# 19_-CAMERA_PWR_CONNECTORS.net
KiCad netlist of a schematic drawn in Altium Designer
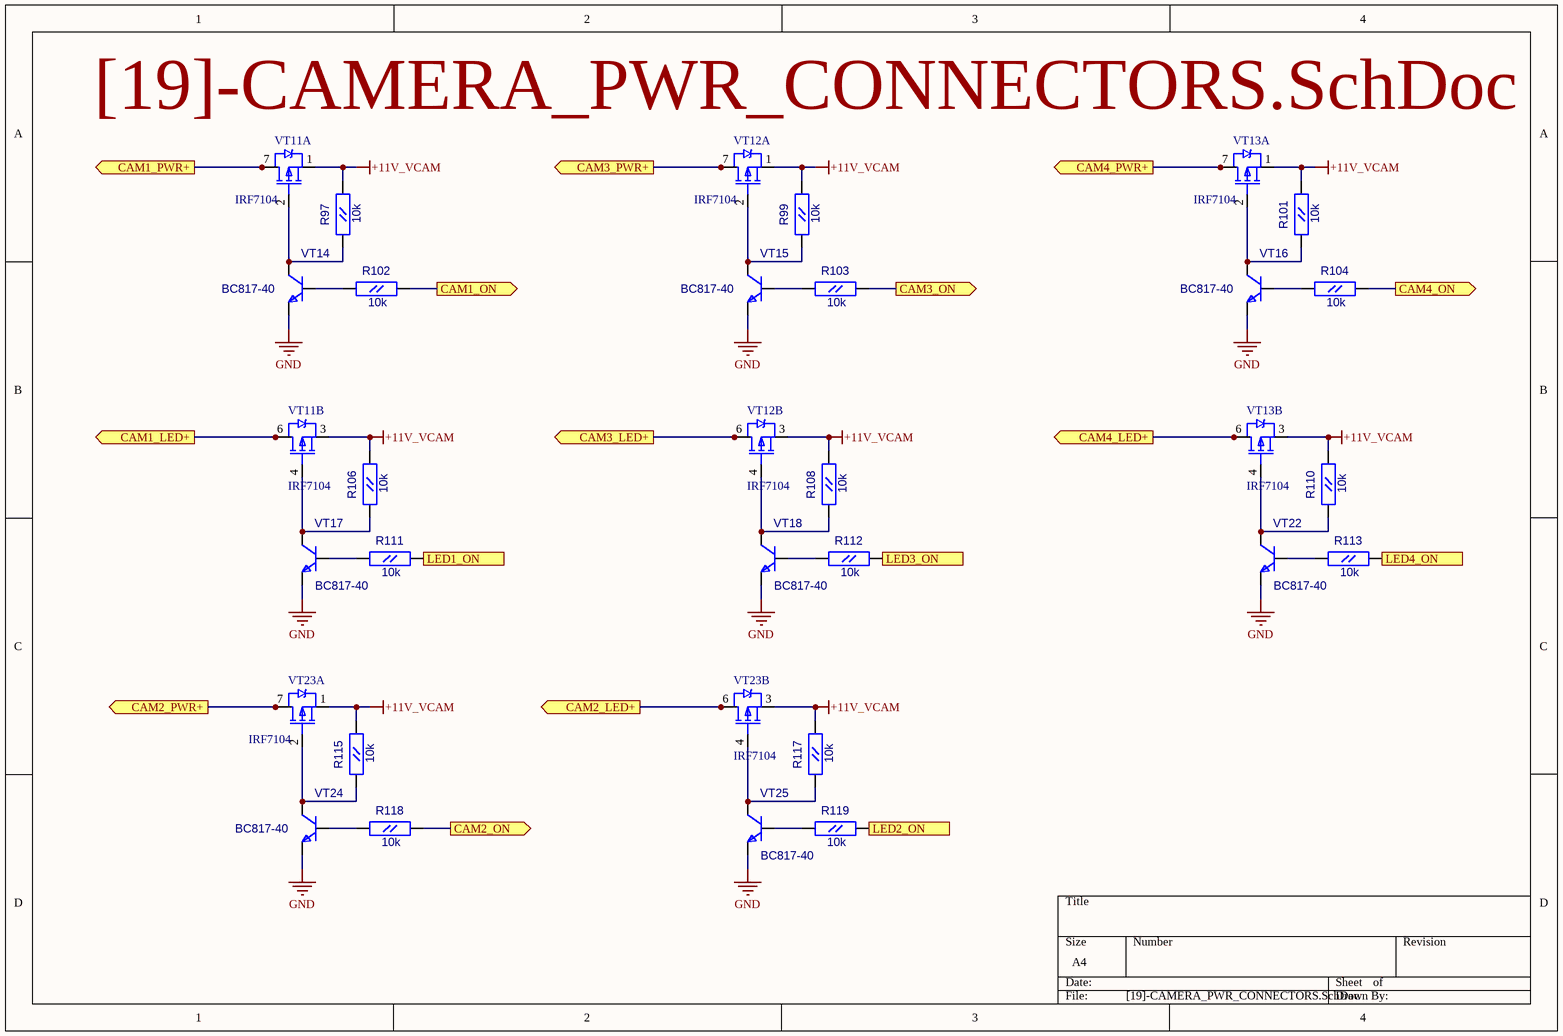
[diagram p0: [19]-CAMERA_PWR_CONNECTORS.SchDoc]

(export (version "E")
  (design (tool "Eeschema 10.0.6"))
  (components
    (comp (ref "R97")
      (value "10k")
      (footprint "RC0603")
      (description "RC0603")
      (libsource (lib "fizik_lib") (part "RC0603"))
    )
    (comp (ref "R99")
      (value "10k")
      (footprint "RC0603")
      (description "RC0603")
      (libsource (lib "fizik_lib") (part "RC0603"))
    )
    (comp (ref "R101")
      (value "10k")
      (footprint "RC0603")
      (description "RC0603")
      (libsource (lib "fizik_lib") (part "RC0603"))
    )
    (comp (ref "R102")
      (value "10k")
      (footprint "RC0603")
      (description "RC0603")
      (libsource (lib "fizik_lib") (part "RC0603"))
    )
    (comp (ref "R103")
      (value "10k")
      (footprint "RC0603")
      (description "RC0603")
      (libsource (lib "fizik_lib") (part "RC0603"))
    )
    (comp (ref "R104")
      (value "10k")
      (footprint "RC0603")
      (description "RC0603")
      (libsource (lib "fizik_lib") (part "RC0603"))
    )
    (comp (ref "R106")
      (value "10k")
      (footprint "RC0603")
      (description "RC0603")
      (libsource (lib "fizik_lib") (part "RC0603"))
    )
    (comp (ref "R108")
      (value "10k")
      (footprint "RC0603")
      (description "RC0603")
      (libsource (lib "fizik_lib") (part "RC0603"))
    )
    (comp (ref "R110")
      (value "10k")
      (footprint "RC0603")
      (description "RC0603")
      (libsource (lib "fizik_lib") (part "RC0603"))
    )
    (comp (ref "R111")
      (value "10k")
      (footprint "RC0603")
      (description "RC0603")
      (libsource (lib "fizik_lib") (part "RC0603"))
    )
    (comp (ref "R112")
      (value "10k")
      (footprint "RC0603")
      (description "RC0603")
      (libsource (lib "fizik_lib") (part "RC0603"))
    )
    (comp (ref "R113")
      (value "10k")
      (footprint "RC0603")
      (description "RC0603")
      (libsource (lib "fizik_lib") (part "RC0603"))
    )
    (comp (ref "R115")
      (value "10k")
      (footprint "RC0603")
      (description "RC0603")
      (libsource (lib "fizik_lib") (part "RC0603"))
    )
    (comp (ref "R117")
      (value "10k")
      (footprint "RC0603")
      (description "RC0603")
      (libsource (lib "fizik_lib") (part "RC0603"))
    )
    (comp (ref "R118")
      (value "10k")
      (footprint "RC0603")
      (description "RC0603")
      (libsource (lib "fizik_lib") (part "RC0603"))
    )
    (comp (ref "R119")
      (value "10k")
      (footprint "RC0603")
      (description "RC0603")
      (libsource (lib "fizik_lib") (part "RC0603"))
    )
    (comp (ref "VT11")
      (value "IRF7104")
      (footprint "SO-8")
      (description "Dual P-channel MOSFET. 20V,2.3A, 0.25Ohm")
      (libsource (lib "fizik_lib (1)") (part "IRF7104"))
    )
    (comp (ref "VT12")
      (value "IRF7104")
      (footprint "SO-8")
      (description "Dual P-channel MOSFET. 20V,2.3A, 0.25Ohm")
      (libsource (lib "fizik_lib (1)") (part "IRF7104"))
    )
    (comp (ref "VT13")
      (value "IRF7104")
      (footprint "SO-8")
      (description "Dual P-channel MOSFET. 20V,2.3A, 0.25Ohm")
      (libsource (lib "fizik_lib (1)") (part "IRF7104"))
    )
    (comp (ref "VT14")
      (value "BC817-40")
      (footprint "SOT-23(123)")
      (description "NPN 500ma transistor")
      (libsource (lib "fizik_lib") (part "BC846BLT1"))
    )
    (comp (ref "VT15")
      (value "BC817-40")
      (footprint "SOT-23(123)")
      (description "NPN 500ma transistor")
      (libsource (lib "fizik_lib") (part "BC846BLT1"))
    )
    (comp (ref "VT16")
      (value "BC817-40")
      (footprint "SOT-23(123)")
      (description "NPN 500ma transistor")
      (libsource (lib "fizik_lib") (part "BC846BLT1"))
    )
    (comp (ref "VT17")
      (value "BC817-40")
      (footprint "SOT-23(123)")
      (description "NPN 500ma transistor")
      (libsource (lib "fizik_lib") (part "BC846BLT1"))
    )
    (comp (ref "VT18")
      (value "BC817-40")
      (footprint "SOT-23(123)")
      (description "NPN 500ma transistor")
      (libsource (lib "fizik_lib") (part "BC846BLT1"))
    )
    (comp (ref "VT22")
      (value "BC817-40")
      (footprint "SOT-23(123)")
      (description "NPN 500ma transistor")
      (libsource (lib "fizik_lib") (part "BC846BLT1"))
    )
    (comp (ref "VT23")
      (value "IRF7104")
      (footprint "SO-8")
      (description "Dual P-channel MOSFET. 20V,2.3A, 0.25Ohm")
      (libsource (lib "fizik_lib (1)") (part "IRF7104"))
    )
    (comp (ref "VT24")
      (value "BC817-40")
      (footprint "SOT-23(123)")
      (description "NPN 500ma transistor")
      (libsource (lib "fizik_lib") (part "BC846BLT1"))
    )
    (comp (ref "VT25")
      (value "BC817-40")
      (footprint "SOT-23(123)")
      (description "NPN 500ma transistor")
      (libsource (lib "fizik_lib") (part "BC846BLT1"))
    )
  )
  (nets
    (net (code "1") (name "+11V_VCAM") (class "Default")
      (node (ref "R101") (pin "2") (pinfunction "B_2") (pintype "passive"))
      (node (ref "R106") (pin "2") (pinfunction "B_2") (pintype "passive"))
      (node (ref "R108") (pin "2") (pinfunction "B_2") (pintype "passive"))
      (node (ref "R110") (pin "2") (pinfunction "B_2") (pintype "passive"))
      (node (ref "R115") (pin "2") (pinfunction "B_2") (pintype "passive"))
      (node (ref "R117") (pin "2") (pinfunction "B_2") (pintype "passive"))
      (node (ref "R97") (pin "2") (pinfunction "B_2") (pintype "passive"))
      (node (ref "R99") (pin "2") (pinfunction "B_2") (pintype "passive"))
      (node (ref "VT11") (pin "1") (pinfunction "S_1") (pintype "passive"))
      (node (ref "VT11") (pin "3") (pinfunction "S_3") (pintype "passive"))
      (node (ref "VT12") (pin "1") (pinfunction "S_1") (pintype "passive"))
      (node (ref "VT12") (pin "3") (pinfunction "S_3") (pintype "passive"))
      (node (ref "VT13") (pin "1") (pinfunction "S_1") (pintype "passive"))
      (node (ref "VT13") (pin "3") (pinfunction "S_3") (pintype "passive"))
      (node (ref "VT23") (pin "1") (pinfunction "S_1") (pintype "passive"))
      (node (ref "VT23") (pin "3") (pinfunction "S_3") (pintype "passive"))
    )
    (net (code "2") (name "/CAM1_LED+") (class "Default")
      (node (ref "VT11") (pin "5") (pinfunction "5_5") (pintype "passive"))
      (node (ref "VT11") (pin "6") (pinfunction "D_6") (pintype "passive"))
    )
    (net (code "3") (name "/CAM1_ON") (class "Default")
      (node (ref "R102") (pin "2") (pinfunction "B_2") (pintype "passive"))
    )
    (net (code "4") (name "/CAM1_PWR+") (class "Default")
      (node (ref "VT11") (pin "7") (pinfunction "D_7") (pintype "passive"))
      (node (ref "VT11") (pin "8") (pinfunction "8_8") (pintype "passive"))
    )
    (net (code "5") (name "/CAM2_LED+") (class "Default")
      (node (ref "VT23") (pin "5") (pinfunction "5_5") (pintype "passive"))
      (node (ref "VT23") (pin "6") (pinfunction "D_6") (pintype "passive"))
    )
    (net (code "6") (name "/CAM2_ON") (class "Default")
      (node (ref "R118") (pin "2") (pinfunction "B_2") (pintype "passive"))
    )
    (net (code "7") (name "/CAM2_PWR+") (class "Default")
      (node (ref "VT23") (pin "7") (pinfunction "D_7") (pintype "passive"))
      (node (ref "VT23") (pin "8") (pinfunction "8_8") (pintype "passive"))
    )
    (net (code "8") (name "/CAM3_LED+") (class "Default")
      (node (ref "VT12") (pin "5") (pinfunction "5_5") (pintype "passive"))
      (node (ref "VT12") (pin "6") (pinfunction "D_6") (pintype "passive"))
    )
    (net (code "9") (name "/CAM3_ON") (class "Default")
      (node (ref "R103") (pin "2") (pinfunction "B_2") (pintype "passive"))
    )
    (net (code "10") (name "/CAM3_PWR+") (class "Default")
      (node (ref "VT12") (pin "7") (pinfunction "D_7") (pintype "passive"))
      (node (ref "VT12") (pin "8") (pinfunction "8_8") (pintype "passive"))
    )
    (net (code "11") (name "/CAM4_LED+") (class "Default")
      (node (ref "VT13") (pin "5") (pinfunction "5_5") (pintype "passive"))
      (node (ref "VT13") (pin "6") (pinfunction "D_6") (pintype "passive"))
    )
    (net (code "12") (name "/CAM4_ON") (class "Default")
      (node (ref "R104") (pin "2") (pinfunction "B_2") (pintype "passive"))
    )
    (net (code "13") (name "/CAM4_PWR+") (class "Default")
      (node (ref "VT13") (pin "7") (pinfunction "D_7") (pintype "passive"))
      (node (ref "VT13") (pin "8") (pinfunction "8_8") (pintype "passive"))
    )
    (net (code "14") (name "/LED1_ON") (class "Default")
      (node (ref "R111") (pin "2") (pinfunction "B_2") (pintype "passive"))
    )
    (net (code "15") (name "/LED2_ON") (class "Default")
      (node (ref "R119") (pin "2") (pinfunction "B_2") (pintype "passive"))
    )
    (net (code "16") (name "/LED3_ON") (class "Default")
      (node (ref "R112") (pin "2") (pinfunction "B_2") (pintype "passive"))
    )
    (net (code "17") (name "/LED4_ON") (class "Default")
      (node (ref "R113") (pin "2") (pinfunction "B_2") (pintype "passive"))
    )
    (net (code "18") (name "GND") (class "Default")
      (node (ref "VT14") (pin "2") (pinfunction "E_2") (pintype "passive"))
      (node (ref "VT15") (pin "2") (pinfunction "E_2") (pintype "passive"))
      (node (ref "VT16") (pin "2") (pinfunction "E_2") (pintype "passive"))
      (node (ref "VT17") (pin "2") (pinfunction "E_2") (pintype "passive"))
      (node (ref "VT18") (pin "2") (pinfunction "E_2") (pintype "passive"))
      (node (ref "VT22") (pin "2") (pinfunction "E_2") (pintype "passive"))
      (node (ref "VT24") (pin "2") (pinfunction "E_2") (pintype "passive"))
      (node (ref "VT25") (pin "2") (pinfunction "E_2") (pintype "passive"))
    )
    (net (code "19") (name "Net-(R97-A)") (class "Default")
      (node (ref "R97") (pin "1") (pinfunction "A_1") (pintype "passive"))
      (node (ref "VT11") (pin "2") (pinfunction "G_2") (pintype "passive"))
      (node (ref "VT14") (pin "3") (pinfunction "C_3") (pintype "passive"))
    )
    (net (code "20") (name "Net-(R99-A)") (class "Default")
      (node (ref "R99") (pin "1") (pinfunction "A_1") (pintype "passive"))
      (node (ref "VT12") (pin "2") (pinfunction "G_2") (pintype "passive"))
      (node (ref "VT15") (pin "3") (pinfunction "C_3") (pintype "passive"))
    )
    (net (code "21") (name "Net-(R101-A)") (class "Default")
      (node (ref "R101") (pin "1") (pinfunction "A_1") (pintype "passive"))
      (node (ref "VT13") (pin "2") (pinfunction "G_2") (pintype "passive"))
      (node (ref "VT16") (pin "3") (pinfunction "C_3") (pintype "passive"))
    )
    (net (code "22") (name "Net-(R102-A)") (class "Default")
      (node (ref "R102") (pin "1") (pinfunction "A_1") (pintype "passive"))
      (node (ref "VT14") (pin "1") (pinfunction "B_1") (pintype "passive"))
    )
    (net (code "23") (name "Net-(R103-A)") (class "Default")
      (node (ref "R103") (pin "1") (pinfunction "A_1") (pintype "passive"))
      (node (ref "VT15") (pin "1") (pinfunction "B_1") (pintype "passive"))
    )
    (net (code "24") (name "Net-(R104-A)") (class "Default")
      (node (ref "R104") (pin "1") (pinfunction "A_1") (pintype "passive"))
      (node (ref "VT16") (pin "1") (pinfunction "B_1") (pintype "passive"))
    )
    (net (code "25") (name "Net-(R106-A)") (class "Default")
      (node (ref "R106") (pin "1") (pinfunction "A_1") (pintype "passive"))
      (node (ref "VT11") (pin "4") (pinfunction "G_4") (pintype "passive"))
      (node (ref "VT17") (pin "3") (pinfunction "C_3") (pintype "passive"))
    )
    (net (code "26") (name "Net-(R108-A)") (class "Default")
      (node (ref "R108") (pin "1") (pinfunction "A_1") (pintype "passive"))
      (node (ref "VT12") (pin "4") (pinfunction "G_4") (pintype "passive"))
      (node (ref "VT18") (pin "3") (pinfunction "C_3") (pintype "passive"))
    )
    (net (code "27") (name "Net-(R110-A)") (class "Default")
      (node (ref "R110") (pin "1") (pinfunction "A_1") (pintype "passive"))
      (node (ref "VT13") (pin "4") (pinfunction "G_4") (pintype "passive"))
      (node (ref "VT22") (pin "3") (pinfunction "C_3") (pintype "passive"))
    )
    (net (code "28") (name "Net-(R111-A)") (class "Default")
      (node (ref "R111") (pin "1") (pinfunction "A_1") (pintype "passive"))
      (node (ref "VT17") (pin "1") (pinfunction "B_1") (pintype "passive"))
    )
    (net (code "29") (name "Net-(R112-A)") (class "Default")
      (node (ref "R112") (pin "1") (pinfunction "A_1") (pintype "passive"))
      (node (ref "VT18") (pin "1") (pinfunction "B_1") (pintype "passive"))
    )
    (net (code "30") (name "Net-(R113-A)") (class "Default")
      (node (ref "R113") (pin "1") (pinfunction "A_1") (pintype "passive"))
      (node (ref "VT22") (pin "1") (pinfunction "B_1") (pintype "passive"))
    )
    (net (code "31") (name "Net-(R115-A)") (class "Default")
      (node (ref "R115") (pin "1") (pinfunction "A_1") (pintype "passive"))
      (node (ref "VT23") (pin "2") (pinfunction "G_2") (pintype "passive"))
      (node (ref "VT24") (pin "3") (pinfunction "C_3") (pintype "passive"))
    )
    (net (code "32") (name "Net-(R117-A)") (class "Default")
      (node (ref "R117") (pin "1") (pinfunction "A_1") (pintype "passive"))
      (node (ref "VT23") (pin "4") (pinfunction "G_4") (pintype "passive"))
      (node (ref "VT25") (pin "3") (pinfunction "C_3") (pintype "passive"))
    )
    (net (code "33") (name "Net-(R118-A)") (class "Default")
      (node (ref "R118") (pin "1") (pinfunction "A_1") (pintype "passive"))
      (node (ref "VT24") (pin "1") (pinfunction "B_1") (pintype "passive"))
    )
    (net (code "34") (name "Net-(R119-A)") (class "Default")
      (node (ref "R119") (pin "1") (pinfunction "A_1") (pintype "passive"))
      (node (ref "VT25") (pin "1") (pinfunction "B_1") (pintype "passive"))
    )
  )
)
